# smartstickSTM32f072.net
KiCad netlist of a schematic drawn in EAGLE
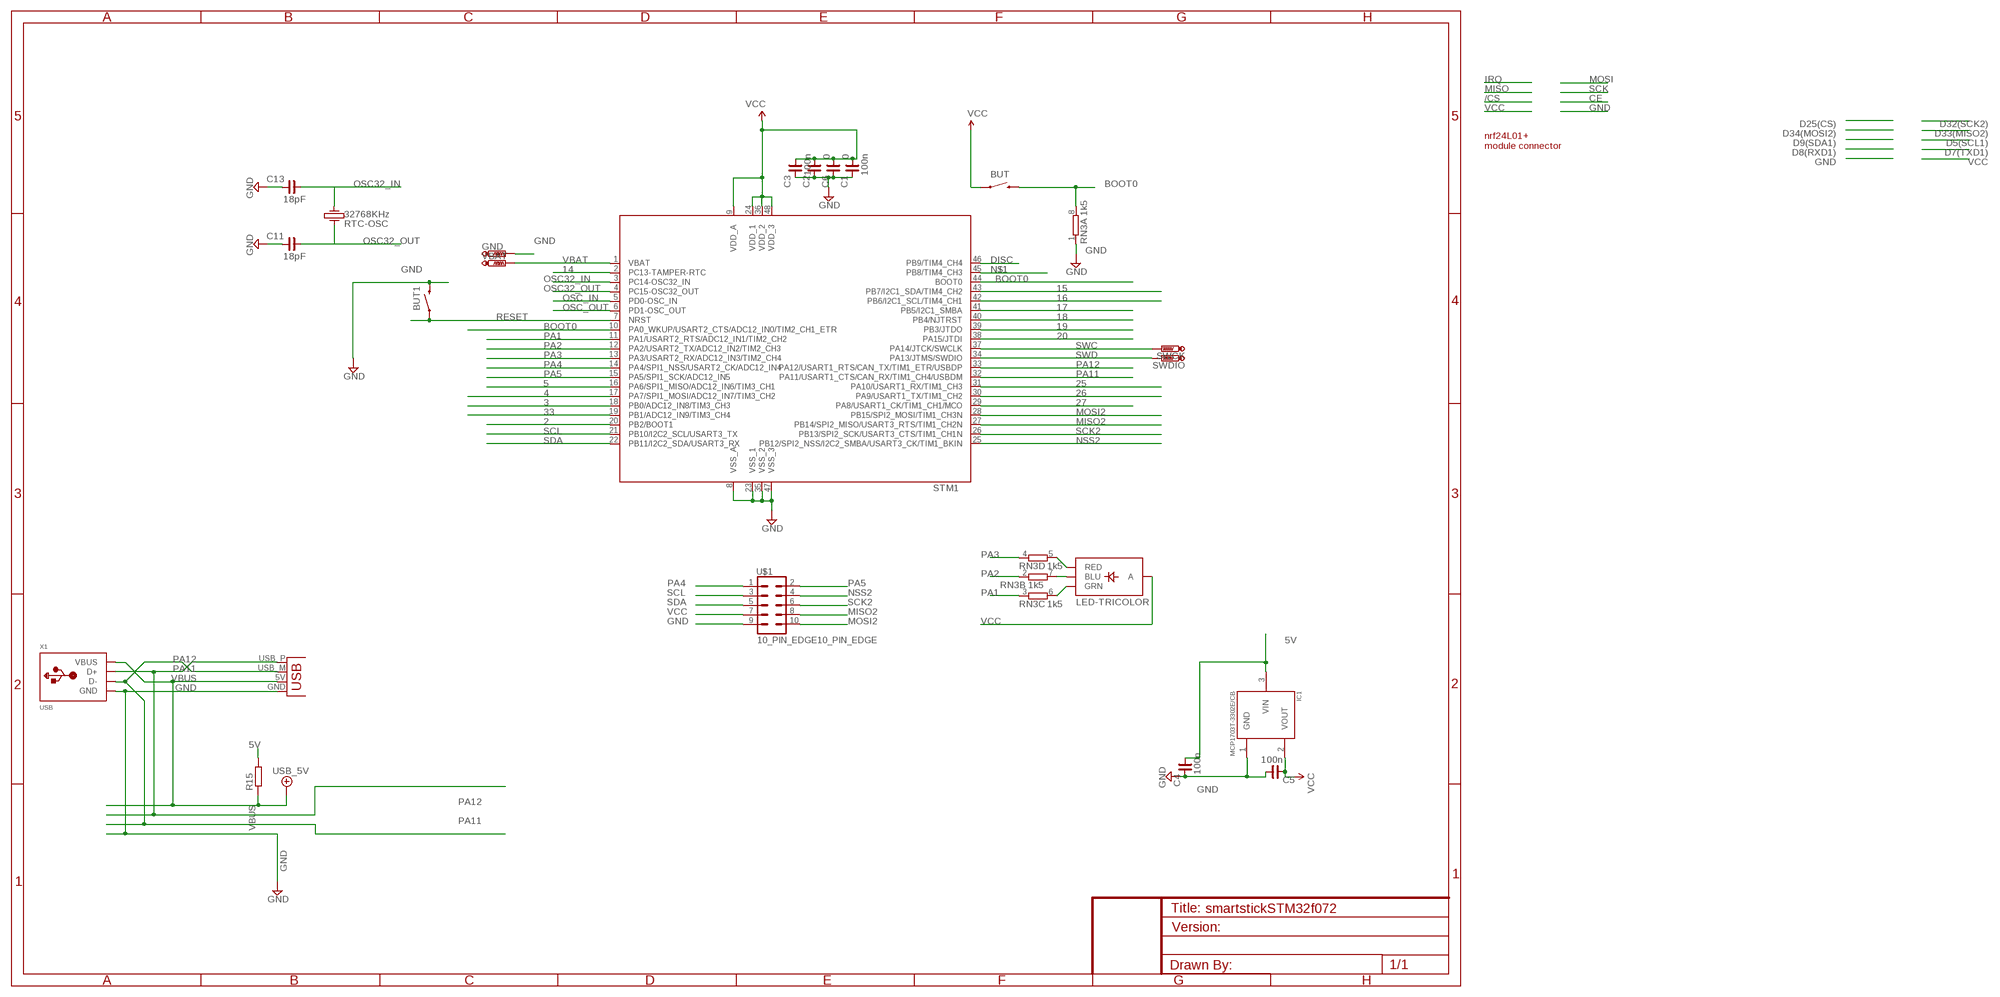
[diagram p0: schematic, sheet 1]

(export (version "E")
  (design (tool "Eeschema 10.0.6"))
  (components
    (comp (ref "BUT")
      (value "SWITCH-MOMENTARY-2-SMD-1101NE")
      (footprint "eagle-import:TACTILE-SWITCH-1101NE")
      (libsource (lib "eagle-import") (part "SWITCH-MOMENTARY-2-SMD-1101NE"))
    )
    (comp (ref "BUT1")
      (value "SWITCH-MOMENTARY-2-SMD-1101NE")
      (footprint "eagle-import:TACTILE-SWITCH-1101NE")
      (libsource (lib "eagle-import") (part "SWITCH-MOMENTARY-2-SMD-1101NE"))
    )
    (comp (ref "C1")
      (value "100n")
      (footprint "eagle-import:C0603")
      (libsource (lib "eagle-import") (part "C_0603"))
    )
    (comp (ref "C2")
      (value "0")
      (footprint "eagle-import:C0603")
      (libsource (lib "eagle-import") (part "C_0603"))
    )
    (comp (ref "C3")
      (value "100n")
      (footprint "eagle-import:C0603")
      (libsource (lib "eagle-import") (part "C_0603"))
    )
    (comp (ref "C4")
      (value "100n")
      (footprint "eagle-import:C0603")
      (libsource (lib "eagle-import") (part "C_0603"))
    )
    (comp (ref "C5")
      (value "100n")
      (footprint "eagle-import:C0603")
      (libsource (lib "eagle-import") (part "C_0603"))
    )
    (comp (ref "C6")
      (value "0")
      (footprint "eagle-import:C0603")
      (libsource (lib "eagle-import") (part "C_0603"))
    )
    (comp (ref "C11")
      (value "18pF")
      (footprint "eagle-import:C0603")
      (libsource (lib "eagle-import") (part "C_0603"))
    )
    (comp (ref "C13")
      (value "18pF")
      (footprint "eagle-import:C0603")
      (libsource (lib "eagle-import") (part "C_0603"))
    )
    (comp (ref "GND")
      (value "PTR1TP20SQ")
      (footprint "eagle-import:TP20SQ")
      (libsource (lib "eagle-import") (part "PTR1TP20SQ"))
    )
    (comp (ref "IC1")
      (value "MCP1703T-3302E/CB")
      (footprint "eagle-import:SOT23")
      (libsource (lib "eagle-import") (part "MCP1700T"))
    )
    (comp (ref "R15")
      (value "R-EU_R0603")
      (footprint "eagle-import:R0603")
      (libsource (lib "eagle-import") (part "R-EU_R0603"))
    )
    (comp (ref "RN3")
      (value "1k5")
      (footprint "eagle-import:EXB38V")
      (libsource (lib "eagle-import") (part "4R-NEXB38V"))
    )
    (comp (ref "RTC-OSC")
      (value "32768KHz")
      (footprint "eagle-import:KX-327LT")
      (libsource (lib "eagle-import") (part "CRYSTALL"))
    )
    (comp (ref "STM1")
      (value "STM32F103CB")
      (footprint "eagle-import:LQFP48")
      (libsource (lib "eagle-import") (part "STM32F103CB"))
    )
    (comp (ref "SWCK")
      (value "PTR1TP16R")
      (footprint "eagle-import:TP16R")
      (libsource (lib "eagle-import") (part "PTR1TP16R"))
    )
    (comp (ref "SWDIO")
      (value "PTR1TP16R")
      (footprint "eagle-import:TP16R")
      (libsource (lib "eagle-import") (part "PTR1TP16R"))
    )
    (comp (ref "U$1")
      (value "10_PIN_EDGE10_PIN_EDGE")
      (footprint "eagle-import:10_PIN_EDGE")
      (libsource (lib "eagle-import") (part "10_PIN_EDGE10_PIN_EDGE"))
    )
    (comp (ref "U$3")
      (value "LED-TRICOLOR")
      (footprint "eagle-import:LED-TRICOLOR-SMD")
      (libsource (lib "eagle-import") (part "LED-TRICOLOR"))
    )
    (comp (ref "VBAT")
      (value "PTR1TP19R")
      (footprint "eagle-import:TP19R")
      (libsource (lib "eagle-import") (part "PTR1TP19R"))
    )
    (comp (ref "X1")
      (value "USB")
      (footprint "eagle-import:MOLEX-48037-1000")
      (libsource (lib "eagle-import") (part "USB"))
    )
    (comp (ref "X3")
      (value "USBPCB")
      (footprint "eagle-import:USB-A-PCB")
      (libsource (lib "eagle-import") (part "USBPCB"))
    )
  )
  (nets
    (net (code "1") (name "/2") (class "Default")
      (node (ref "STM1") (pin "20") (pinfunction "PB2/BOOT1_20") (pintype "bidirectional"))
    )
    (net (code "2") (name "/3") (class "Default")
      (node (ref "STM1") (pin "18") (pinfunction "PB0/ADC12_IN8/TIM3_CH3_18") (pintype "bidirectional"))
    )
    (net (code "3") (name "/4") (class "Default")
      (node (ref "STM1") (pin "17") (pinfunction "PA7/SPI1_MOSI/ADC12_IN7/TIM3_CH2_17") (pintype "bidirectional"))
    )
    (net (code "4") (name "/5") (class "Default")
      (node (ref "STM1") (pin "16") (pinfunction "PA6/SPI1_MISO/ADC12_IN6/TIM3_CH1_16") (pintype "bidirectional"))
    )
    (net (code "5") (name "/5V") (class "Default")
      (node (ref "C4") (pin "1") (pinfunction "1_1") (pintype "passive"))
      (node (ref "IC1") (pin "3") (pinfunction "VIN_3") (pintype "bidirectional"))
      (node (ref "R15") (pin "2") (pinfunction "2_2") (pintype "passive"))
    )
    (net (code "6") (name "/14") (class "Default")
      (node (ref "STM1") (pin "2") (pinfunction "PC13-TAMPER-RTC_2") (pintype "input"))
    )
    (net (code "7") (name "/15") (class "Default")
      (node (ref "STM1") (pin "43") (pinfunction "PB7/I2C1_SDA/TIM4_CH2_43") (pintype "bidirectional"))
    )
    (net (code "8") (name "/16") (class "Default")
      (node (ref "STM1") (pin "42") (pinfunction "PB6/I2C1_SCL/TIM4_CH1_42") (pintype "input"))
    )
    (net (code "9") (name "/17") (class "Default")
      (node (ref "STM1") (pin "41") (pinfunction "PB5/I2C1_SMBA_41") (pintype "input"))
    )
    (net (code "10") (name "/18") (class "Default")
      (node (ref "STM1") (pin "40") (pinfunction "PB4/NJTRST_40") (pintype "bidirectional"))
    )
    (net (code "11") (name "/19") (class "Default")
      (node (ref "STM1") (pin "39") (pinfunction "PB3/JTDO_39") (pintype "bidirectional"))
    )
    (net (code "12") (name "/20") (class "Default")
      (node (ref "STM1") (pin "38") (pinfunction "PA15/JTDI_38") (pintype "bidirectional"))
    )
    (net (code "13") (name "/25") (class "Default")
      (node (ref "STM1") (pin "31") (pinfunction "PA10/USART1_RX/TIM1_CH3_31") (pintype "bidirectional"))
    )
    (net (code "14") (name "/26") (class "Default")
      (node (ref "STM1") (pin "30") (pinfunction "PA9/USART1_TX/TIM1_CH2_30") (pintype "input"))
    )
    (net (code "15") (name "/27") (class "Default")
      (node (ref "STM1") (pin "29") (pinfunction "PA8/USART1_CK/TIM1_CH1/MCO_29") (pintype "bidirectional"))
    )
    (net (code "16") (name "/33") (class "Default")
      (node (ref "STM1") (pin "19") (pinfunction "PB1/ADC12_IN9/TIM3_CH4_19") (pintype "bidirectional"))
    )
    (net (code "17") (name "/BOOT0") (class "Default")
      (node (ref "BUT") (pin "P$2") (pinfunction "2_P$2") (pintype "passive"))
      (node (ref "RN3") (pin "8") (pinfunction "2_8") (pintype "passive"))
      (node (ref "STM1") (pin "10") (pinfunction "PA0_WKUP/USART2_CTS/ADC12_IN0/TIM2_CH1_ETR_10") (pintype "bidirectional"))
      (node (ref "STM1") (pin "44") (pinfunction "BOOT0_44") (pintype "input"))
    )
    (net (code "27") (name "/DISC") (class "Default")
      (node (ref "STM1") (pin "46") (pinfunction "PB9/TIM4_CH4_46") (pintype "input"))
    )
    (net (code "30") (name "/MISO2") (class "Default")
      (node (ref "STM1") (pin "27") (pinfunction "PB14/SPI2_MISO/USART3_RTS/TIM1_CH2N_27") (pintype "input"))
      (node (ref "U$1") (pin "8") (pinfunction "8_8") (pintype "passive"))
    )
    (net (code "32") (name "/MOSI2") (class "Default")
      (node (ref "STM1") (pin "28") (pinfunction "PB15/SPI2_MOSI/TIM1_CH3N_28") (pintype "input"))
      (node (ref "U$1") (pin "10") (pinfunction "10_10") (pintype "passive"))
    )
    (net (code "33") (name "/N$1") (class "Default")
      (node (ref "STM1") (pin "45") (pinfunction "PB8/TIM4_CH3_45") (pintype "bidirectional"))
    )
    (net (code "34") (name "/NSS2") (class "Default")
      (node (ref "STM1") (pin "25") (pinfunction "PB12/SPI2_NSS/I2C2_SMBA/USART3_CK/TIM1_BKIN_25") (pintype "input"))
      (node (ref "U$1") (pin "4") (pinfunction "4_4") (pintype "passive"))
    )
    (net (code "35") (name "/OSC32_IN") (class "Default")
      (node (ref "C13") (pin "1") (pinfunction "1_1") (pintype "passive"))
      (node (ref "RTC-OSC") (pin "1") (pinfunction "P$1_1") (pintype "bidirectional"))
      (node (ref "STM1") (pin "3") (pinfunction "PC14-OSC32_IN_3") (pintype "input"))
    )
    (net (code "36") (name "/OSC32_OUT") (class "Default")
      (node (ref "C11") (pin "1") (pinfunction "1_1") (pintype "passive"))
      (node (ref "RTC-OSC") (pin "4") (pinfunction "P$2_4") (pintype "bidirectional"))
      (node (ref "STM1") (pin "4") (pinfunction "PC15-OSC32_OUT_4") (pintype "input"))
    )
    (net (code "37") (name "/OSC_IN") (class "Default")
      (node (ref "STM1") (pin "5") (pinfunction "PD0-OSC_IN_5") (pintype "input"))
    )
    (net (code "38") (name "/OSC_OUT") (class "Default")
      (node (ref "STM1") (pin "6") (pinfunction "PD1-OSC_OUT_6") (pintype "input"))
    )
    (net (code "39") (name "/PA1") (class "Default")
      (node (ref "RN3") (pin "3") (pinfunction "1_3") (pintype "passive"))
      (node (ref "STM1") (pin "11") (pinfunction "PA1/USART2_RTS/ADC12_IN1/TIM2_CH2_11") (pintype "bidirectional"))
    )
    (net (code "40") (name "/PA2") (class "Default")
      (node (ref "RN3") (pin "2") (pinfunction "1_2") (pintype "passive"))
      (node (ref "STM1") (pin "12") (pinfunction "PA2/USART2_TX/ADC12_IN2/TIM2_CH3_12") (pintype "bidirectional"))
    )
    (net (code "41") (name "/PA3") (class "Default")
      (node (ref "RN3") (pin "4") (pinfunction "1_4") (pintype "passive"))
      (node (ref "STM1") (pin "13") (pinfunction "PA3/USART2_RX/ADC12_IN3/TIM2_CH4_13") (pintype "bidirectional"))
    )
    (net (code "42") (name "/PA4") (class "Default")
      (node (ref "STM1") (pin "14") (pinfunction "PA4/SPI1_NSS/USART2_CK/ADC12_IN4_14") (pintype "bidirectional"))
      (node (ref "U$1") (pin "1") (pinfunction "1_1") (pintype "passive"))
    )
    (net (code "43") (name "/PA5") (class "Default")
      (node (ref "STM1") (pin "15") (pinfunction "PA5/SPI1_SCK/ADC12_IN5_15") (pintype "bidirectional"))
      (node (ref "U$1") (pin "2") (pinfunction "2_2") (pintype "passive"))
    )
    (net (code "44") (name "/PA11") (class "Default")
      (node (ref "STM1") (pin "32") (pinfunction "PA11/USART1_CTS/CAN_RX/TIM1_CH4/USBDM_32") (pintype "bidirectional"))
      (node (ref "X1") (pin "2") (pinfunction "D-_2") (pintype "bidirectional"))
      (node (ref "X3") (pin "USB_M") (pinfunction "D-_USB_M") (pintype "bidirectional"))
    )
    (net (code "45") (name "/PA12") (class "Default")
      (node (ref "STM1") (pin "33") (pinfunction "PA12/USART1_RTS/CAN_TX/TIM1_ETR/USBDP_33") (pintype "bidirectional"))
      (node (ref "X1") (pin "3") (pinfunction "D+_3") (pintype "bidirectional"))
      (node (ref "X3") (pin "USB_P") (pinfunction "D+_USB_P") (pintype "bidirectional"))
    )
    (net (code "46") (name "/RESET") (class "Default")
      (node (ref "BUT1") (pin "P$1") (pinfunction "1_P$1") (pintype "passive"))
      (node (ref "STM1") (pin "7") (pinfunction "NRST_7") (pintype "input"))
    )
    (net (code "48") (name "/SCK2") (class "Default")
      (node (ref "STM1") (pin "26") (pinfunction "PB13/SPI2_SCK/USART3_CTS/TIM1_CH1N_26") (pintype "input"))
      (node (ref "U$1") (pin "6") (pinfunction "6_6") (pintype "passive"))
    )
    (net (code "49") (name "/SCL") (class "Default")
      (node (ref "STM1") (pin "21") (pinfunction "PB10/I2C2_SCL/USART3_TX_21") (pintype "input"))
      (node (ref "U$1") (pin "3") (pinfunction "3_3") (pintype "passive"))
    )
    (net (code "50") (name "/SDA") (class "Default")
      (node (ref "STM1") (pin "22") (pinfunction "PB11/I2C2_SDA/USART3_RX_22") (pintype "input"))
      (node (ref "U$1") (pin "5") (pinfunction "5_5") (pintype "passive"))
    )
    (net (code "51") (name "/SWC") (class "Default")
      (node (ref "STM1") (pin "37") (pinfunction "PA14/JTCK/SWCLK_37") (pintype "bidirectional"))
      (node (ref "SWCK") (pin "TP") (pinfunction "TP_TP") (pintype "input"))
    )
    (net (code "52") (name "/SWD") (class "Default")
      (node (ref "STM1") (pin "34") (pinfunction "PA13/JTMS/SWDIO_34") (pintype "bidirectional"))
      (node (ref "SWDIO") (pin "TP") (pinfunction "TP_TP") (pintype "input"))
    )
    (net (code "53") (name "/VBAT") (class "Default")
      (node (ref "STM1") (pin "1") (pinfunction "VBAT_1") (pintype "power_in"))
      (node (ref "VBAT") (pin "TP") (pinfunction "TP_TP") (pintype "input"))
    )
    (net (code "55") (name "GND") (class "Default")
      (node (ref "BUT1") (pin "P$2") (pinfunction "2_P$2") (pintype "passive"))
      (node (ref "C1") (pin "2") (pinfunction "2_2") (pintype "passive"))
      (node (ref "C11") (pin "2") (pinfunction "2_2") (pintype "passive"))
      (node (ref "C13") (pin "2") (pinfunction "2_2") (pintype "passive"))
      (node (ref "C2") (pin "2") (pinfunction "2_2") (pintype "passive"))
      (node (ref "C3") (pin "2") (pinfunction "2_2") (pintype "passive"))
      (node (ref "C4") (pin "2") (pinfunction "2_2") (pintype "passive"))
      (node (ref "C5") (pin "1") (pinfunction "1_1") (pintype "passive"))
      (node (ref "C6") (pin "2") (pinfunction "2_2") (pintype "passive"))
      (node (ref "GND") (pin "TP") (pinfunction "TP_TP") (pintype "input"))
      (node (ref "IC1") (pin "1") (pinfunction "GND_1") (pintype "bidirectional"))
      (node (ref "RN3") (pin "1") (pinfunction "1_1") (pintype "passive"))
      (node (ref "STM1") (pin "23") (pinfunction "VSS_1_23") (pintype "power_in"))
      (node (ref "STM1") (pin "35") (pinfunction "VSS_2_35") (pintype "power_in"))
      (node (ref "STM1") (pin "47") (pinfunction "VSS_3_47") (pintype "power_in"))
      (node (ref "STM1") (pin "8") (pinfunction "VSS_A_8") (pintype "power_in"))
      (node (ref "U$1") (pin "9") (pinfunction "9_9") (pintype "passive"))
      (node (ref "X1") (pin "4") (pinfunction "GND_4") (pintype "power_in"))
      (node (ref "X3") (pin "GND") (pinfunction "GND_GND") (pintype "bidirectional"))
    )
    (net (code "56") (name "Net-(RN3B-2)") (class "Default")
      (node (ref "RN3") (pin "7") (pinfunction "2_7") (pintype "passive"))
      (node (ref "U$3") (pin "B") (pinfunction "BLU_B") (pintype "bidirectional"))
    )
    (net (code "57") (name "Net-(RN3C-2)") (class "Default")
      (node (ref "RN3") (pin "6") (pinfunction "2_6") (pintype "passive"))
      (node (ref "U$3") (pin "G") (pinfunction "GRN_G") (pintype "bidirectional"))
    )
    (net (code "58") (name "Net-(RN3D-2)") (class "Default")
      (node (ref "RN3") (pin "5") (pinfunction "2_5") (pintype "passive"))
      (node (ref "U$3") (pin "R") (pinfunction "RED_R") (pintype "bidirectional"))
    )
    (net (code "59") (name "USB_5V") (class "Default")
      (node (ref "R15") (pin "1") (pinfunction "1_1") (pintype "passive"))
      (node (ref "X1") (pin "1") (pinfunction "VBUS_1") (pintype "power_in"))
      (node (ref "X3") (pin "5V") (pinfunction "VBUS_5V") (pintype "bidirectional"))
    )
    (net (code "60") (name "VCC") (class "Default")
      (node (ref "BUT") (pin "P$1") (pinfunction "1_P$1") (pintype "passive"))
      (node (ref "C1") (pin "1") (pinfunction "1_1") (pintype "passive"))
      (node (ref "C2") (pin "1") (pinfunction "1_1") (pintype "passive"))
      (node (ref "C3") (pin "1") (pinfunction "1_1") (pintype "passive"))
      (node (ref "C5") (pin "2") (pinfunction "2_2") (pintype "passive"))
      (node (ref "C6") (pin "1") (pinfunction "1_1") (pintype "passive"))
      (node (ref "IC1") (pin "2") (pinfunction "VOUT_2") (pintype "bidirectional"))
      (node (ref "STM1") (pin "24") (pinfunction "VDD_1_24") (pintype "power_in"))
      (node (ref "STM1") (pin "36") (pinfunction "VDD_2_36") (pintype "power_in"))
      (node (ref "STM1") (pin "48") (pinfunction "VDD_3_48") (pintype "power_in"))
      (node (ref "STM1") (pin "9") (pinfunction "VDD_A_9") (pintype "power_in"))
      (node (ref "U$1") (pin "7") (pinfunction "7_7") (pintype "passive"))
      (node (ref "U$3") (pin "A") (pinfunction "A_A") (pintype "bidirectional"))
    )
  )
)
